# main.net
KiCad netlist of a schematic drawn in EAGLE
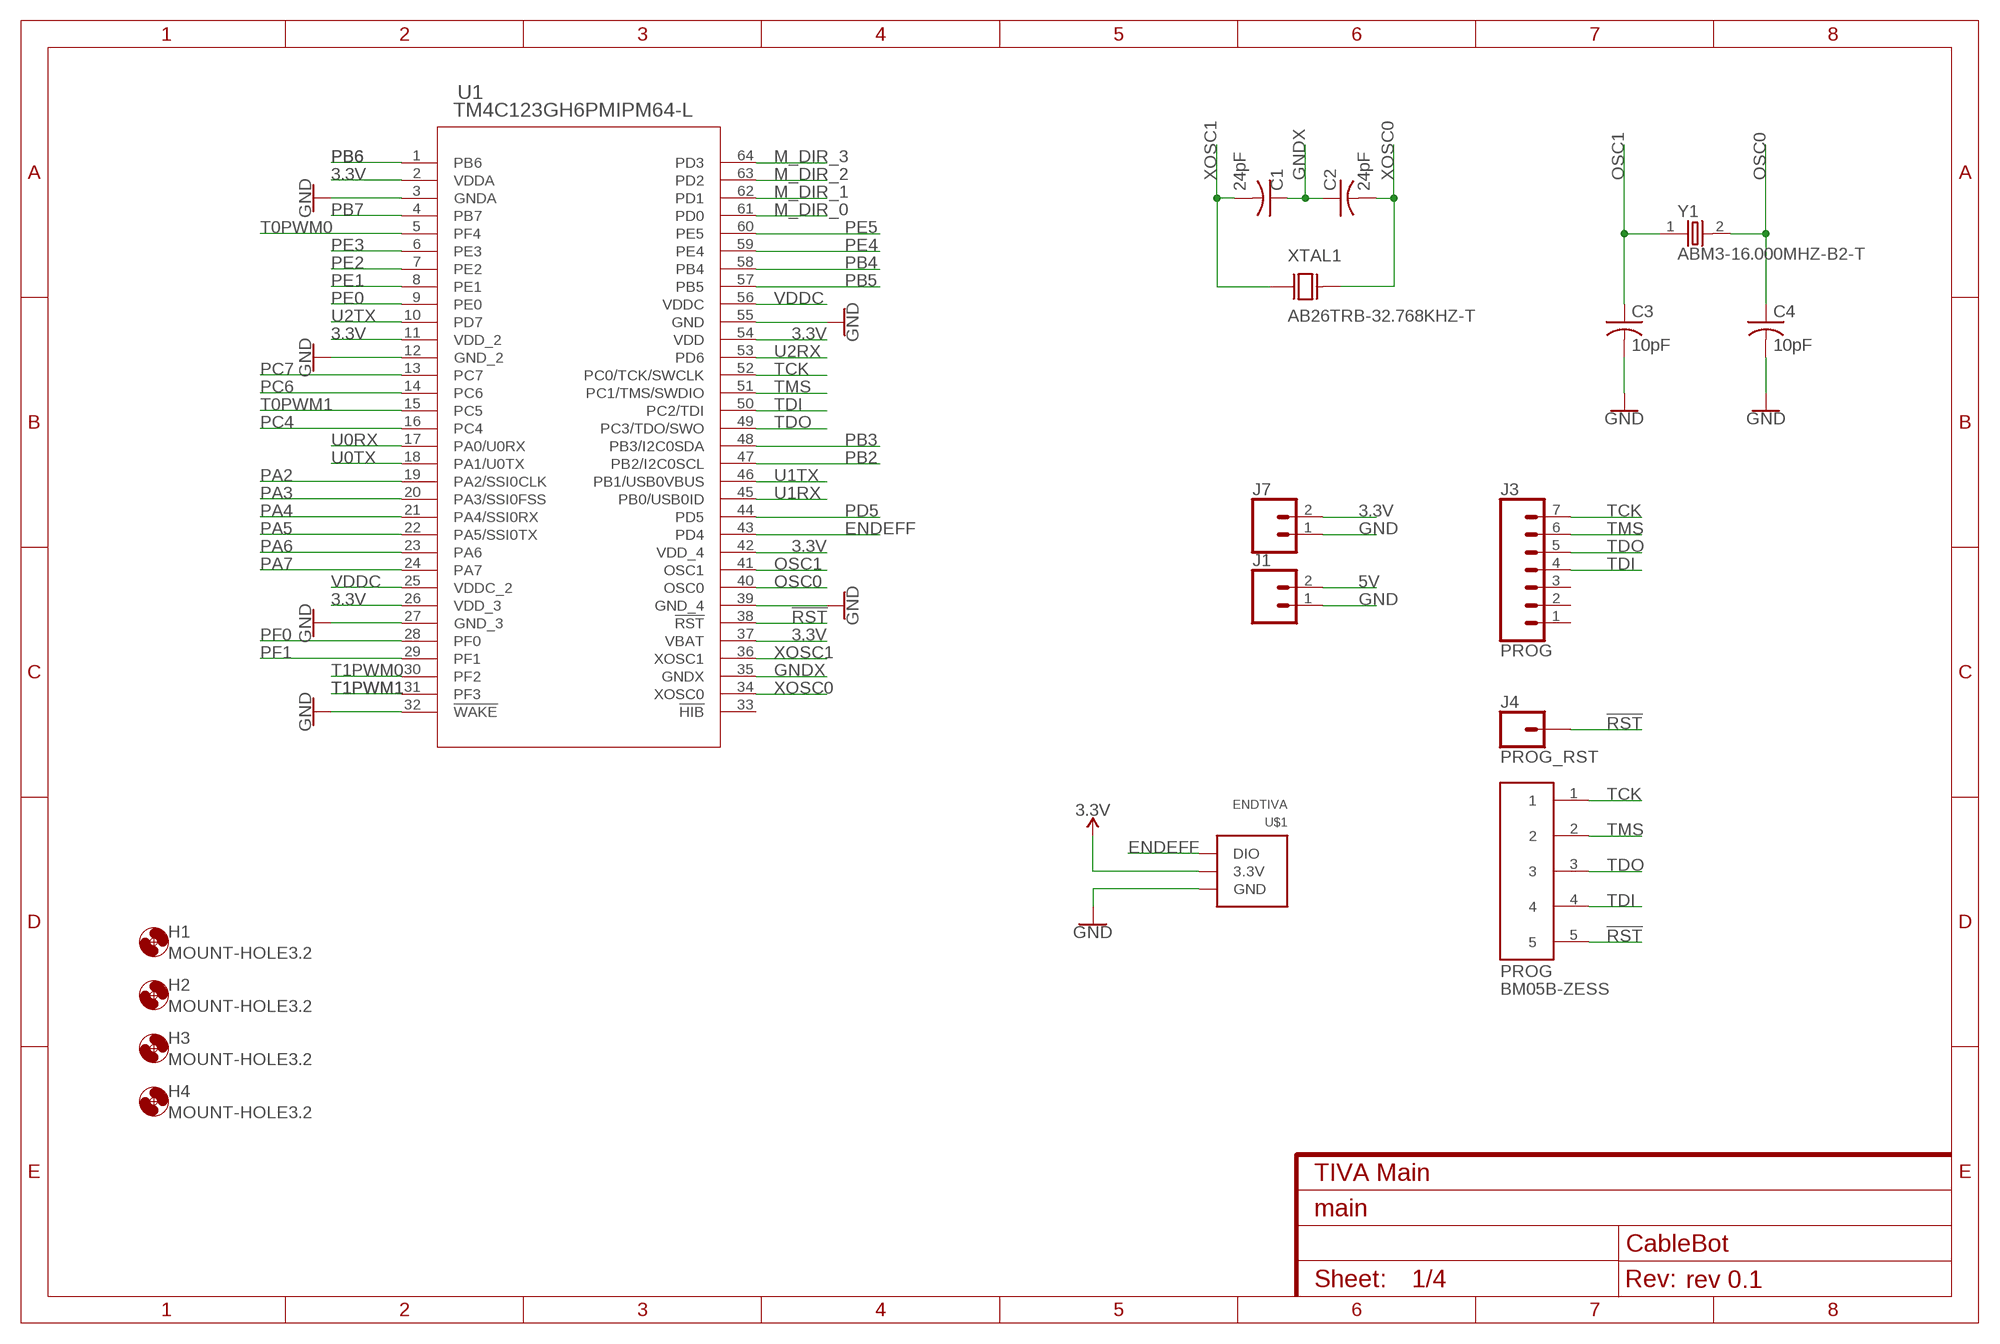
[diagram p0: schematic, sheet 1]
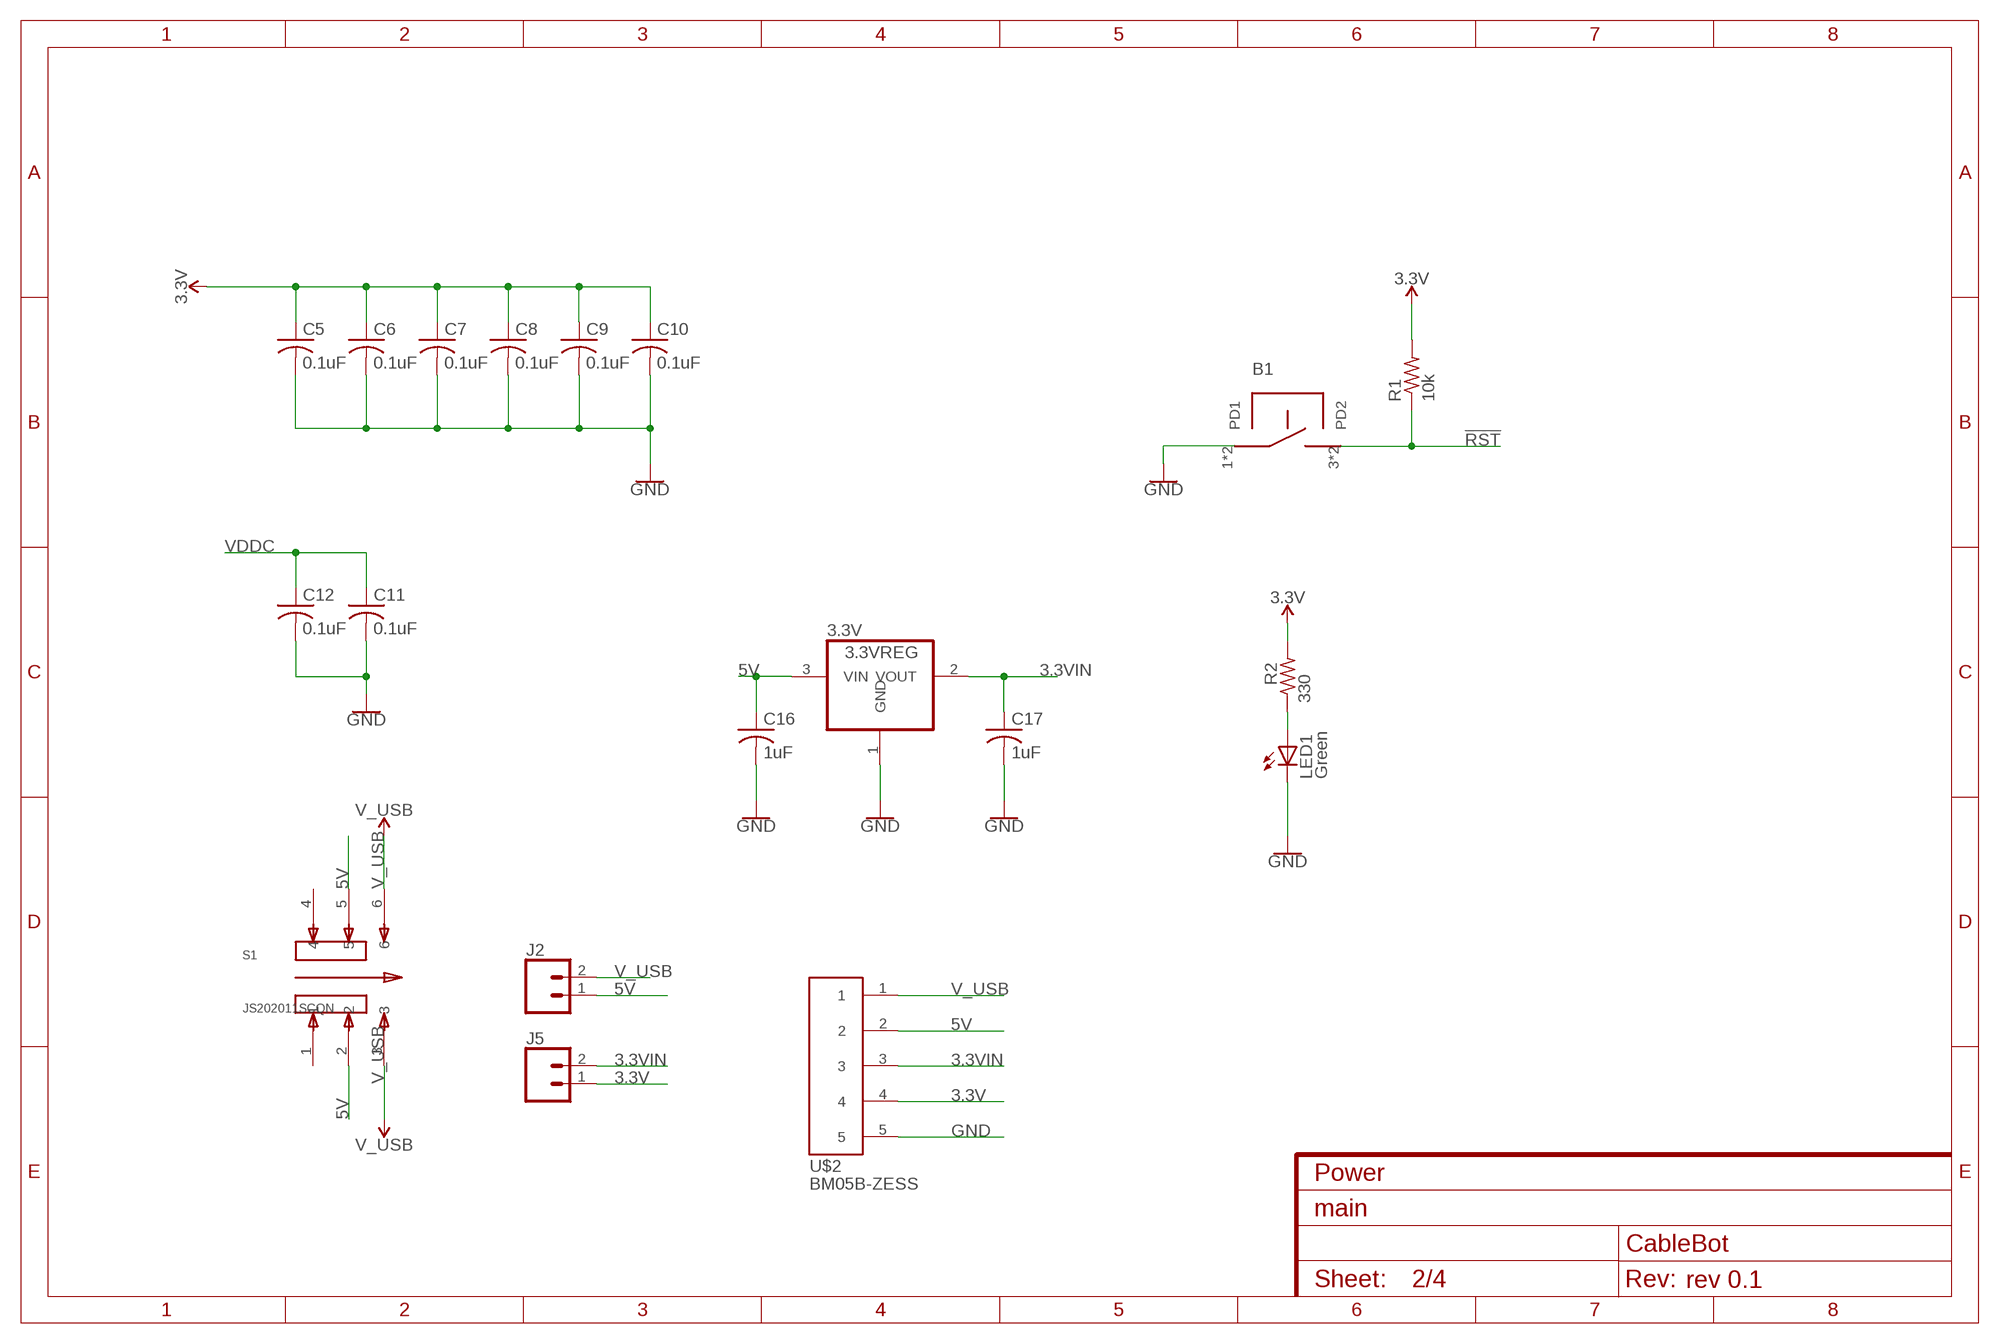
[diagram p1: schematic, sheet 2]
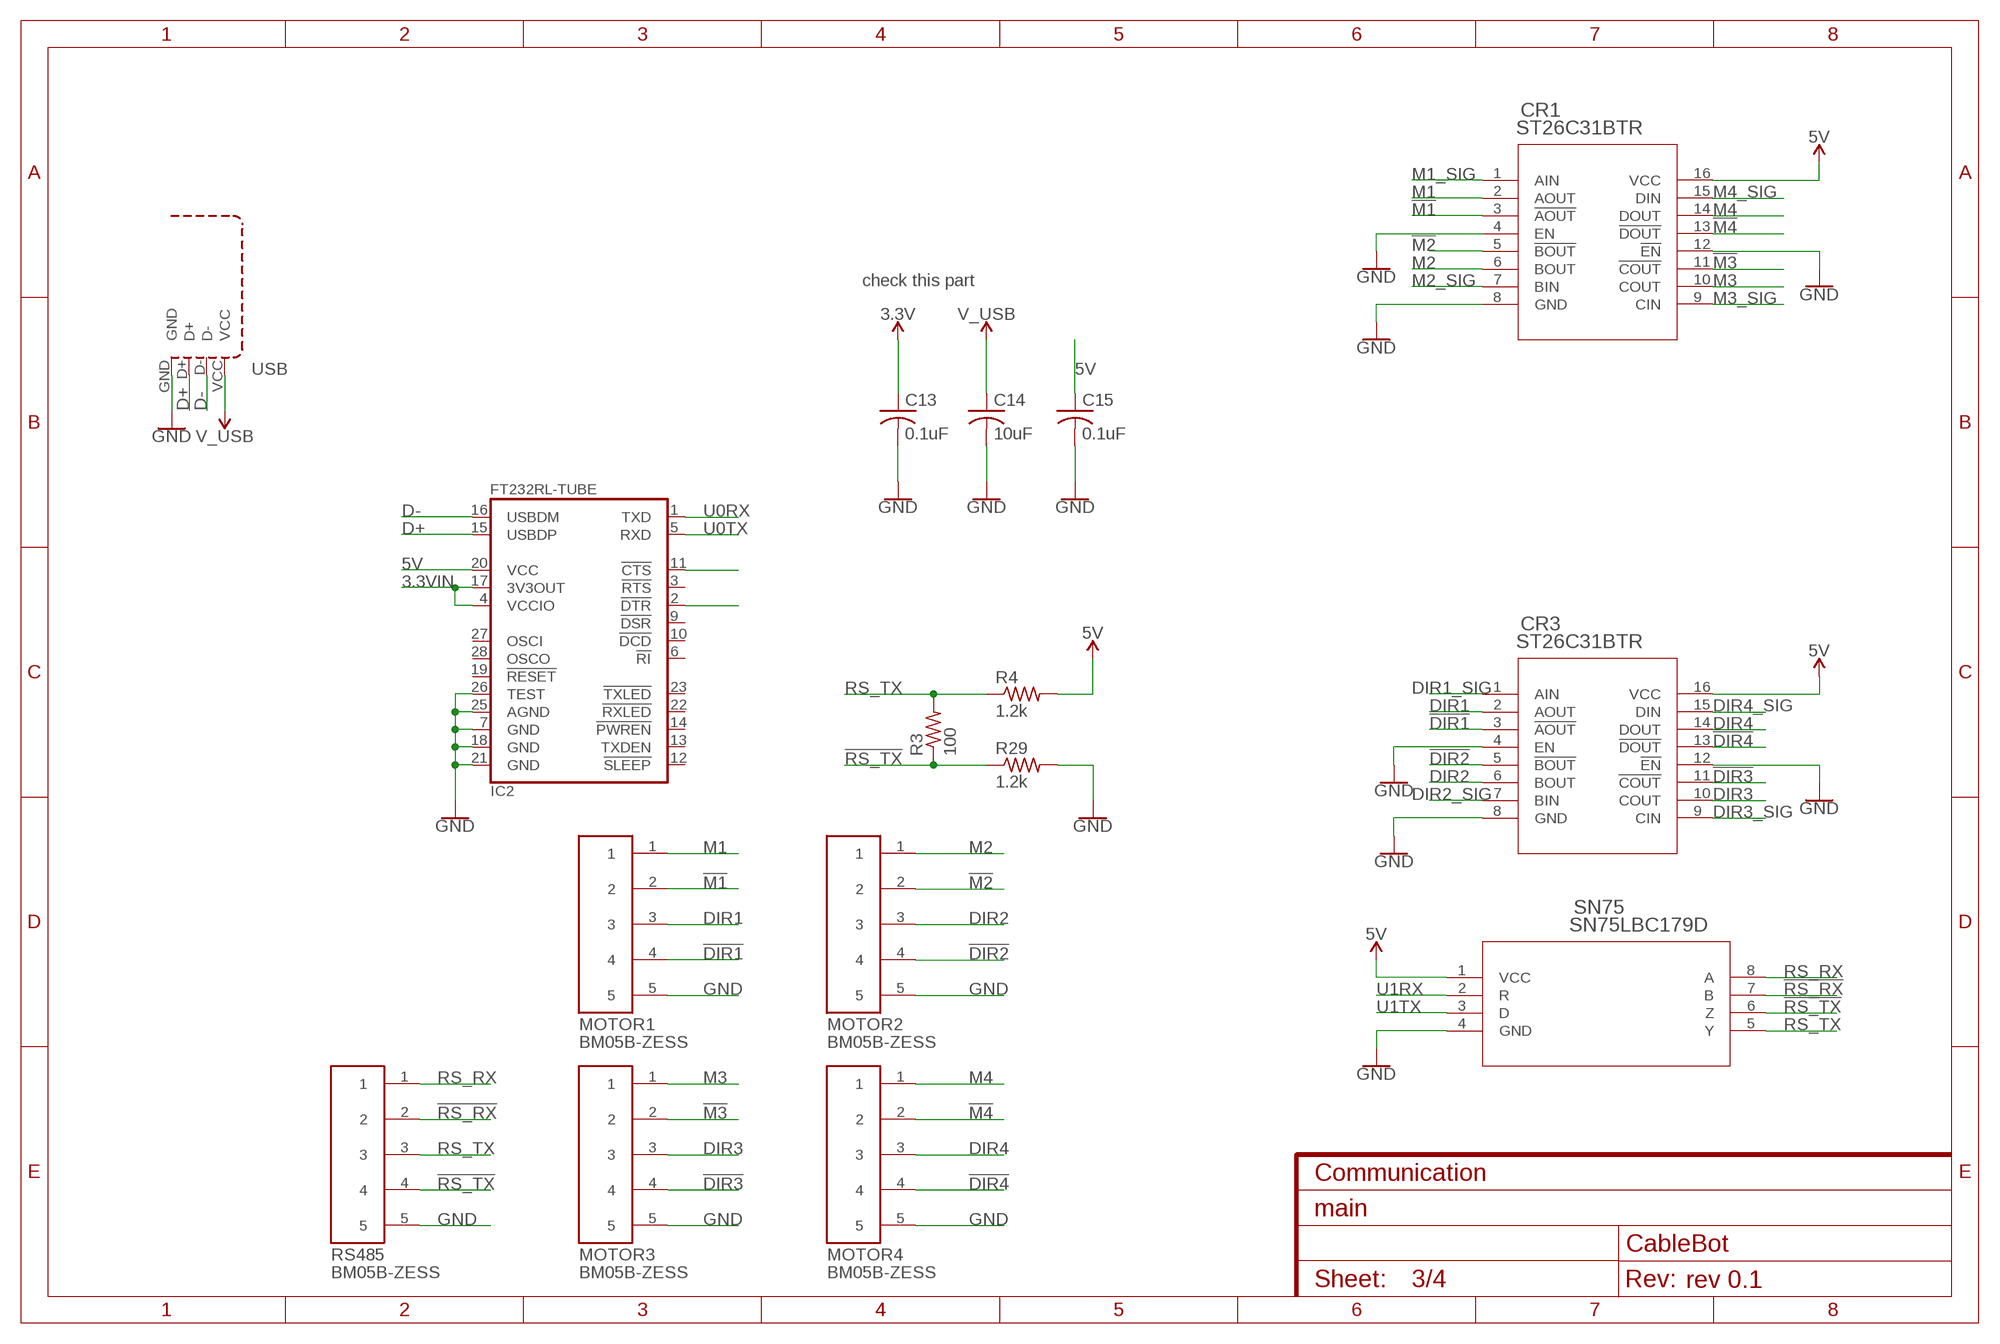
[diagram p2: schematic, sheet 3]
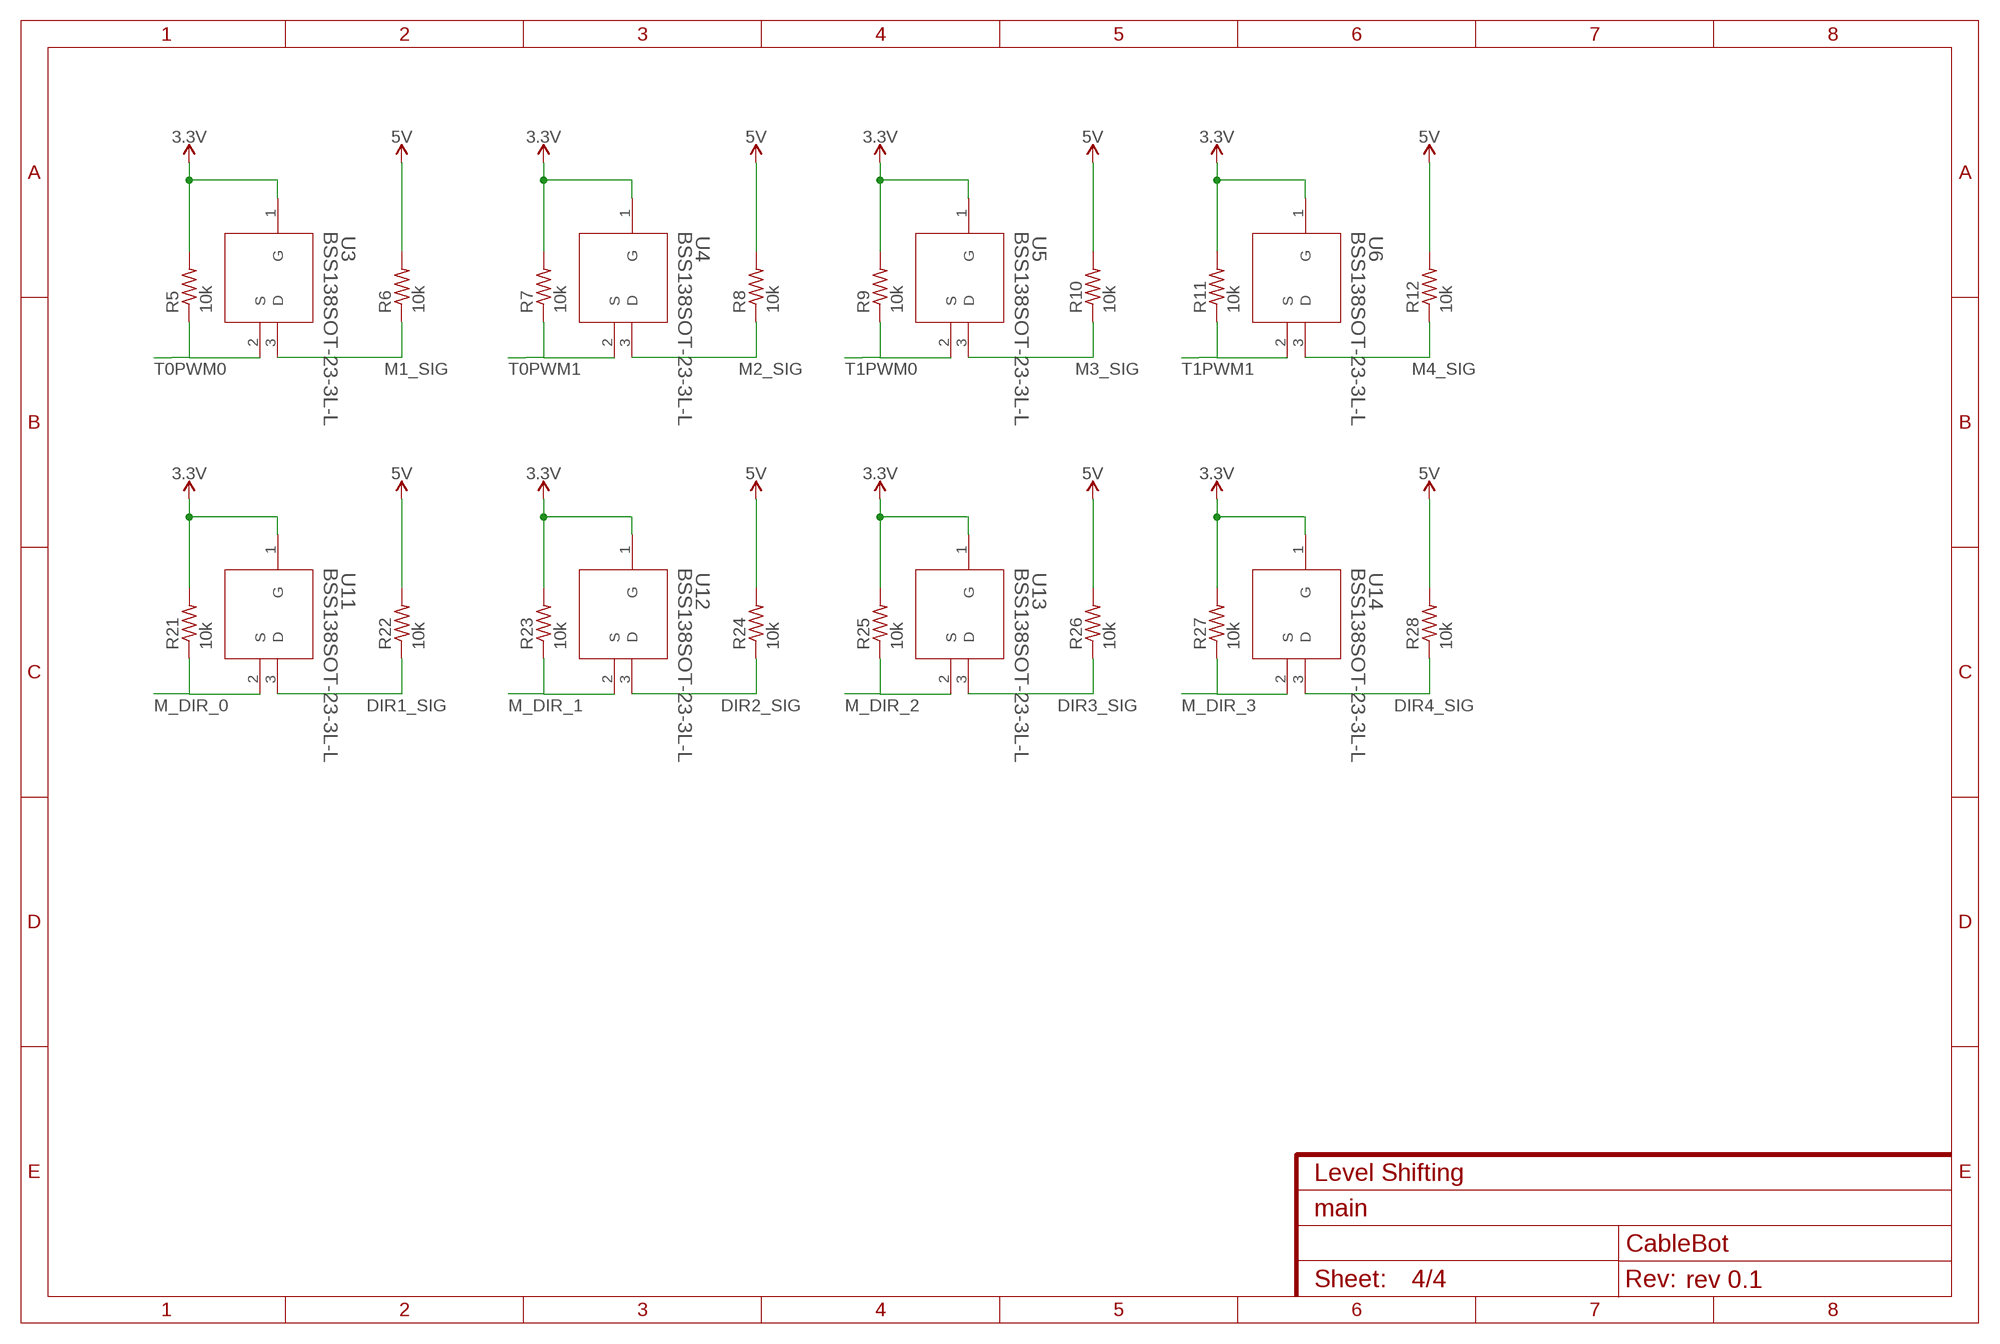
[diagram p3: schematic, sheet 4]

(export (version "E")
  (design (tool "Eeschema 10.0.6"))
  (components
    (comp (ref "3.3V")
      (value "3.3VREG")
      (footprint "eagle-import:SOT223")
      (fields (field (name "MPN") "REG1117"))
      (libsource (lib "eagle-import") (part "REG1117"))
    )
    (comp (ref "B1")
      (value "B3S-1000")
      (footprint "eagle-import:SWITCH")
      (libsource (lib "eagle-import") (part "B3S-1000"))
    )
    (comp (ref "C5")
      (value "0.1uF")
      (footprint "eagle-import:C0805")
      (libsource (lib "eagle-import") (part "C-USC0805"))
    )
    (comp (ref "C6")
      (value "0.1uF")
      (footprint "eagle-import:C0805")
      (libsource (lib "eagle-import") (part "C-USC0805"))
    )
    (comp (ref "C7")
      (value "0.1uF")
      (footprint "eagle-import:C0805")
      (libsource (lib "eagle-import") (part "C-USC0805"))
    )
    (comp (ref "C8")
      (value "0.1uF")
      (footprint "eagle-import:C0805")
      (libsource (lib "eagle-import") (part "C-USC0805"))
    )
    (comp (ref "C9")
      (value "0.1uF")
      (footprint "eagle-import:C0805")
      (libsource (lib "eagle-import") (part "C-USC0805"))
    )
    (comp (ref "C10")
      (value "0.1uF")
      (footprint "eagle-import:C0805")
      (libsource (lib "eagle-import") (part "C-USC0805"))
    )
    (comp (ref "C11")
      (value "0.1uF")
      (footprint "eagle-import:C0805")
      (libsource (lib "eagle-import") (part "C-USC0805"))
    )
    (comp (ref "C12")
      (value "0.1uF")
      (footprint "eagle-import:C0805")
      (libsource (lib "eagle-import") (part "C-USC0805"))
    )
    (comp (ref "C16")
      (value "1uF")
      (footprint "eagle-import:C0805")
      (libsource (lib "eagle-import") (part "C-USC0805"))
    )
    (comp (ref "C17")
      (value "1uF")
      (footprint "eagle-import:C0805")
      (libsource (lib "eagle-import") (part "C-USC0805"))
    )
    (comp (ref "J2")
      (value "CONN_02")
      (footprint "eagle-import:1X02")
      (libsource (lib "eagle-import") (part "CONN_02"))
    )
    (comp (ref "J5")
      (value "CONN_02")
      (footprint "eagle-import:1X02")
      (libsource (lib "eagle-import") (part "CONN_02"))
    )
    (comp (ref "LED1")
      (value "Green")
      (footprint "eagle-import:CHIP-LED0805")
      (libsource (lib "eagle-import") (part "LEDCHIP-LED0805"))
    )
    (comp (ref "R1")
      (value "10k")
      (footprint "eagle-import:R0603")
      (libsource (lib "eagle-import") (part "adafruit_420_R-US_R0603"))
    )
    (comp (ref "R2")
      (value "330")
      (footprint "eagle-import:R0805")
      (libsource (lib "eagle-import") (part "adafruit_420_R-US_R0805"))
    )
    (comp (ref "S1")
      (value "JS202011SCQN")
      (footprint "eagle-import:SW_JS202011SCQN")
      (fields (field (name "MF") "C&K"))
      (libsource (lib "eagle-import") (part "JS202011SCQN"))
    )
    (comp (ref "U$2")
      (value "BM05B-ZESS")
      (footprint "eagle-import:BM05B-ZESS")
      (libsource (lib "eagle-import") (part "BM05B-ZESS"))
    )
    (comp (ref "C1")
      (value "24pF")
      (footprint "eagle-import:C0805")
      (libsource (lib "eagle-import") (part "C-USC0805"))
    )
    (comp (ref "C2")
      (value "24pF")
      (footprint "eagle-import:C0805")
      (libsource (lib "eagle-import") (part "C-USC0805"))
    )
    (comp (ref "C3")
      (value "10pF")
      (footprint "eagle-import:C0805")
      (libsource (lib "eagle-import") (part "C-USC0805"))
    )
    (comp (ref "C4")
      (value "10pF")
      (footprint "eagle-import:C0805")
      (libsource (lib "eagle-import") (part "C-USC0805"))
    )
    (comp (ref "H1")
      (value "MOUNT-HOLE3.2")
      (footprint "eagle-import:3,2")
      (libsource (lib "eagle-import") (part "MOUNT-HOLE3.2"))
    )
    (comp (ref "H2")
      (value "MOUNT-HOLE3.2")
      (footprint "eagle-import:3,2")
      (libsource (lib "eagle-import") (part "MOUNT-HOLE3.2"))
    )
    (comp (ref "H3")
      (value "MOUNT-HOLE3.2")
      (footprint "eagle-import:3,2")
      (libsource (lib "eagle-import") (part "MOUNT-HOLE3.2"))
    )
    (comp (ref "H4")
      (value "MOUNT-HOLE3.2")
      (footprint "eagle-import:3,2")
      (libsource (lib "eagle-import") (part "MOUNT-HOLE3.2"))
    )
    (comp (ref "J1")
      (value "CONN_02")
      (footprint "eagle-import:1X02")
      (libsource (lib "eagle-import") (part "CONN_02"))
    )
    (comp (ref "J3")
      (value "PROG")
      (footprint "eagle-import:1X07")
      (libsource (lib "eagle-import") (part "CONN_07"))
    )
    (comp (ref "J4")
      (value "PROG_RST")
      (footprint "eagle-import:1X01")
      (libsource (lib "eagle-import") (part "CONN_01"))
    )
    (comp (ref "J7")
      (value "CONN_02")
      (footprint "eagle-import:1X02")
      (libsource (lib "eagle-import") (part "CONN_02"))
    )
    (comp (ref "PROG")
      (value "BM05B-ZESS")
      (footprint "eagle-import:BM05B-ZESS")
      (libsource (lib "eagle-import") (part "BM05B-ZESS"))
    )
    (comp (ref "U$1")
      (value "ENDTIVA")
      (footprint "eagle-import:ENDTIVA")
      (libsource (lib "eagle-import") (part "ENDTIVA"))
    )
    (comp (ref "U1")
      (value "TM4C123GH6PMIPM64-L")
      (footprint "eagle-import:PM64-L")
      (fields (field (name "MANUFACTURER_PART_NUMBER") "TM4C123GH6PMI"))
      (libsource (lib "eagle-import") (part "TM4C123GH6PMIPM64-L"))
    )
    (comp (ref "XTAL1")
      (value "AB26TRB-32.768KHZ-T")
      (footprint "eagle-import:XTAL_AB26TRB-32.768KHZ-T")
      (fields (field (name "DIGI-KEY_PART_NUMBER") "535-9033-1-ND") (field (name "MF") "Abracon"))
      (libsource (lib "eagle-import") (part "AB26TRB-32.768KHZ-T"))
    )
    (comp (ref "Y1")
      (value "ABM3-16.000MHZ-B2-T")
      (footprint "eagle-import:XTAL500X320X130N")
      (fields (field (name "DIGI-KEY_PART_NUMBER") "535-9103-1-ND") (field (name "MF") "Abracon"))
      (libsource (lib "eagle-import") (part "ABM3-16.000MHZ-B2-T"))
    )
    (comp (ref "R5")
      (value "10k")
      (footprint "eagle-import:R0603")
      (libsource (lib "eagle-import") (part "R-US_R0603"))
    )
    (comp (ref "R6")
      (value "10k")
      (footprint "eagle-import:R0603")
      (libsource (lib "eagle-import") (part "R-US_R0603"))
    )
    (comp (ref "R7")
      (value "10k")
      (footprint "eagle-import:R0603")
      (libsource (lib "eagle-import") (part "R-US_R0603"))
    )
    (comp (ref "R8")
      (value "10k")
      (footprint "eagle-import:R0603")
      (libsource (lib "eagle-import") (part "R-US_R0603"))
    )
    (comp (ref "R9")
      (value "10k")
      (footprint "eagle-import:R0603")
      (libsource (lib "eagle-import") (part "R-US_R0603"))
    )
    (comp (ref "R10")
      (value "10k")
      (footprint "eagle-import:R0603")
      (libsource (lib "eagle-import") (part "R-US_R0603"))
    )
    (comp (ref "R11")
      (value "10k")
      (footprint "eagle-import:R0603")
      (libsource (lib "eagle-import") (part "R-US_R0603"))
    )
    (comp (ref "R12")
      (value "10k")
      (footprint "eagle-import:R0603")
      (libsource (lib "eagle-import") (part "R-US_R0603"))
    )
    (comp (ref "R21")
      (value "10k")
      (footprint "eagle-import:R0603")
      (libsource (lib "eagle-import") (part "R-US_R0603"))
    )
    (comp (ref "R22")
      (value "10k")
      (footprint "eagle-import:R0603")
      (libsource (lib "eagle-import") (part "R-US_R0603"))
    )
    (comp (ref "R23")
      (value "10k")
      (footprint "eagle-import:R0603")
      (libsource (lib "eagle-import") (part "R-US_R0603"))
    )
    (comp (ref "R24")
      (value "10k")
      (footprint "eagle-import:R0603")
      (libsource (lib "eagle-import") (part "R-US_R0603"))
    )
    (comp (ref "R25")
      (value "10k")
      (footprint "eagle-import:R0603")
      (libsource (lib "eagle-import") (part "R-US_R0603"))
    )
    (comp (ref "R26")
      (value "10k")
      (footprint "eagle-import:R0603")
      (libsource (lib "eagle-import") (part "R-US_R0603"))
    )
    (comp (ref "R27")
      (value "10k")
      (footprint "eagle-import:R0603")
      (libsource (lib "eagle-import") (part "R-US_R0603"))
    )
    (comp (ref "R28")
      (value "10k")
      (footprint "eagle-import:R0603")
      (libsource (lib "eagle-import") (part "R-US_R0603"))
    )
    (comp (ref "U3")
      (value "BSS138SOT-23-3L-L")
      (footprint "eagle-import:SOT-23-3L-L")
      (fields (field (name "MANUFACTURER_PART_NUMBER") "BSS138"))
      (libsource (lib "eagle-import") (part "BSS138SOT-23-3L-L"))
    )
    (comp (ref "U4")
      (value "BSS138SOT-23-3L-L")
      (footprint "eagle-import:SOT-23-3L-L")
      (fields (field (name "MANUFACTURER_PART_NUMBER") "BSS138"))
      (libsource (lib "eagle-import") (part "BSS138SOT-23-3L-L"))
    )
    (comp (ref "U5")
      (value "BSS138SOT-23-3L-L")
      (footprint "eagle-import:SOT-23-3L-L")
      (fields (field (name "MANUFACTURER_PART_NUMBER") "BSS138"))
      (libsource (lib "eagle-import") (part "BSS138SOT-23-3L-L"))
    )
    (comp (ref "U6")
      (value "BSS138SOT-23-3L-L")
      (footprint "eagle-import:SOT-23-3L-L")
      (fields (field (name "MANUFACTURER_PART_NUMBER") "BSS138"))
      (libsource (lib "eagle-import") (part "BSS138SOT-23-3L-L"))
    )
    (comp (ref "U11")
      (value "BSS138SOT-23-3L-L")
      (footprint "eagle-import:SOT-23-3L-L")
      (fields (field (name "MANUFACTURER_PART_NUMBER") "BSS138"))
      (libsource (lib "eagle-import") (part "BSS138SOT-23-3L-L"))
    )
    (comp (ref "U12")
      (value "BSS138SOT-23-3L-L")
      (footprint "eagle-import:SOT-23-3L-L")
      (fields (field (name "MANUFACTURER_PART_NUMBER") "BSS138"))
      (libsource (lib "eagle-import") (part "BSS138SOT-23-3L-L"))
    )
    (comp (ref "U13")
      (value "BSS138SOT-23-3L-L")
      (footprint "eagle-import:SOT-23-3L-L")
      (fields (field (name "MANUFACTURER_PART_NUMBER") "BSS138"))
      (libsource (lib "eagle-import") (part "BSS138SOT-23-3L-L"))
    )
    (comp (ref "U14")
      (value "BSS138SOT-23-3L-L")
      (footprint "eagle-import:SOT-23-3L-L")
      (fields (field (name "MANUFACTURER_PART_NUMBER") "BSS138"))
      (libsource (lib "eagle-import") (part "BSS138SOT-23-3L-L"))
    )
    (comp (ref "C13")
      (value "0.1uF")
      (footprint "eagle-import:C0805")
      (libsource (lib "eagle-import") (part "C-USC0805"))
    )
    (comp (ref "C14")
      (value "10uF")
      (footprint "eagle-import:C0805")
      (libsource (lib "eagle-import") (part "C-USC0805"))
    )
    (comp (ref "C15")
      (value "0.1uF")
      (footprint "eagle-import:C0805")
      (libsource (lib "eagle-import") (part "C-USC0805"))
    )
    (comp (ref "CR1")
      (value "ST26C31BTR")
      (footprint "eagle-import:TSSOP16")
      (libsource (lib "eagle-import") (part "ST26C31BTR"))
    )
    (comp (ref "CR3")
      (value "ST26C31BTR")
      (footprint "eagle-import:TSSOP16")
      (libsource (lib "eagle-import") (part "ST26C31BTR"))
    )
    (comp (ref "IC2")
      (value "FT232RL-TUBE")
      (footprint "eagle-import:SSOP28-LD")
      (fields (field (name "DIGI-KEY_PART_NUMBER") "768-1306-ND") (field (name "MF") "FTDI,"))
      (libsource (lib "eagle-import") (part "FT232RL-TUBE"))
    )
    (comp (ref "MOTOR1")
      (value "BM05B-ZESS")
      (footprint "eagle-import:BM05B-ZESS")
      (libsource (lib "eagle-import") (part "BM05B-ZESS"))
    )
    (comp (ref "MOTOR2")
      (value "BM05B-ZESS")
      (footprint "eagle-import:BM05B-ZESS")
      (libsource (lib "eagle-import") (part "BM05B-ZESS"))
    )
    (comp (ref "MOTOR3")
      (value "BM05B-ZESS")
      (footprint "eagle-import:BM05B-ZESS")
      (libsource (lib "eagle-import") (part "BM05B-ZESS"))
    )
    (comp (ref "MOTOR4")
      (value "BM05B-ZESS")
      (footprint "eagle-import:BM05B-ZESS")
      (libsource (lib "eagle-import") (part "BM05B-ZESS"))
    )
    (comp (ref "R3")
      (value "100")
      (footprint "eagle-import:R0805")
      (libsource (lib "eagle-import") (part "resistor_348_R-US_R0805"))
    )
    (comp (ref "R4")
      (value "1.2k")
      (footprint "eagle-import:R0805")
      (libsource (lib "eagle-import") (part "resistor_348_R-US_R0805"))
    )
    (comp (ref "R29")
      (value "1.2k")
      (footprint "eagle-import:R0805")
      (libsource (lib "eagle-import") (part "resistor_348_R-US_R0805"))
    )
    (comp (ref "RS485")
      (value "BM05B-ZESS")
      (footprint "eagle-import:BM05B-ZESS")
      (libsource (lib "eagle-import") (part "BM05B-ZESS"))
    )
    (comp (ref "SN75")
      (value "SN75LBC179D")
      (footprint "eagle-import:D8")
      (libsource (lib "eagle-import") (part "SN75LBC179D"))
    )
    (comp (ref "USB")
      (value "ZX62MICROUSB")
      (footprint "eagle-import:ZX62-AB-5PA(11)")
      (libsource (lib "eagle-import") (part "ZX62MICROUSB"))
    )
  )
  (nets
    (net (code "1") (name "3.3V") (class "Default")
      (node (ref "C10") (pin "1") (pinfunction "1_1") (pintype "passive"))
      (node (ref "C13") (pin "1") (pinfunction "1_1") (pintype "passive"))
      (node (ref "C5") (pin "1") (pinfunction "1_1") (pintype "passive"))
      (node (ref "C6") (pin "1") (pinfunction "1_1") (pintype "passive"))
      (node (ref "C7") (pin "1") (pinfunction "1_1") (pintype "passive"))
      (node (ref "C8") (pin "1") (pinfunction "1_1") (pintype "passive"))
      (node (ref "C9") (pin "1") (pinfunction "1_1") (pintype "passive"))
      (node (ref "J5") (pin "1") (pinfunction "1_1") (pintype "passive"))
      (node (ref "J7") (pin "2") (pinfunction "2_2") (pintype "passive"))
      (node (ref "R1") (pin "2") (pinfunction "2_2") (pintype "passive"))
      (node (ref "R11") (pin "2") (pinfunction "2_2") (pintype "passive"))
      (node (ref "R2") (pin "2") (pinfunction "2_2") (pintype "passive"))
      (node (ref "R21") (pin "2") (pinfunction "2_2") (pintype "passive"))
      (node (ref "R23") (pin "2") (pinfunction "2_2") (pintype "passive"))
      (node (ref "R25") (pin "2") (pinfunction "2_2") (pintype "passive"))
      (node (ref "R27") (pin "2") (pinfunction "2_2") (pintype "passive"))
      (node (ref "R5") (pin "2") (pinfunction "2_2") (pintype "passive"))
      (node (ref "R7") (pin "2") (pinfunction "2_2") (pintype "passive"))
      (node (ref "R9") (pin "2") (pinfunction "2_2") (pintype "passive"))
      (node (ref "U$1") (pin "3.3V") (pinfunction "3.3V_3.3V") (pintype "bidirectional"))
      (node (ref "U$2") (pin "4") (pinfunction "4_4") (pintype "bidirectional"))
      (node (ref "U1") (pin "11") (pinfunction "VDD_2_11") (pintype "power_in"))
      (node (ref "U1") (pin "2") (pinfunction "VDDA_2") (pintype "power_in"))
      (node (ref "U1") (pin "26") (pinfunction "VDD_3_26") (pintype "power_in"))
      (node (ref "U1") (pin "37") (pinfunction "VBAT_37") (pintype "power_in"))
      (node (ref "U1") (pin "42") (pinfunction "VDD_4_42") (pintype "power_in"))
      (node (ref "U1") (pin "54") (pinfunction "VDD_54") (pintype "power_in"))
      (node (ref "U11") (pin "1") (pinfunction "G_1") (pintype "passive"))
      (node (ref "U12") (pin "1") (pinfunction "G_1") (pintype "passive"))
      (node (ref "U13") (pin "1") (pinfunction "G_1") (pintype "passive"))
      (node (ref "U14") (pin "1") (pinfunction "G_1") (pintype "passive"))
      (node (ref "U3") (pin "1") (pinfunction "G_1") (pintype "passive"))
      (node (ref "U4") (pin "1") (pinfunction "G_1") (pintype "passive"))
      (node (ref "U5") (pin "1") (pinfunction "G_1") (pintype "passive"))
      (node (ref "U6") (pin "1") (pinfunction "G_1") (pintype "passive"))
    )
    (net (code "2") (name "3.3VIN") (class "Default")
      (node (ref "3.3V") (pin "2") (pinfunction "VOUT_2") (pintype "output"))
      (node (ref "C17") (pin "1") (pinfunction "1_1") (pintype "passive"))
      (node (ref "IC2") (pin "17") (pinfunction "3V3OUT_17") (pintype "power_in"))
      (node (ref "IC2") (pin "4") (pinfunction "VCCIO_4") (pintype "power_in"))
      (node (ref "J5") (pin "2") (pinfunction "2_2") (pintype "passive"))
      (node (ref "U$2") (pin "3") (pinfunction "3_3") (pintype "bidirectional"))
    )
    (net (code "3") (name "5V") (class "Default")
      (node (ref "3.3V") (pin "3") (pinfunction "VIN_3") (pintype "input"))
      (node (ref "C15") (pin "1") (pinfunction "1_1") (pintype "passive"))
      (node (ref "C16") (pin "1") (pinfunction "1_1") (pintype "passive"))
      (node (ref "CR1") (pin "16") (pinfunction "VCC_16") (pintype "power_in"))
      (node (ref "CR3") (pin "16") (pinfunction "VCC_16") (pintype "power_in"))
      (node (ref "IC2") (pin "20") (pinfunction "VCC_20") (pintype "power_in"))
      (node (ref "J1") (pin "2") (pinfunction "2_2") (pintype "passive"))
      (node (ref "J2") (pin "1") (pinfunction "1_1") (pintype "passive"))
      (node (ref "R10") (pin "2") (pinfunction "2_2") (pintype "passive"))
      (node (ref "R12") (pin "2") (pinfunction "2_2") (pintype "passive"))
      (node (ref "R22") (pin "2") (pinfunction "2_2") (pintype "passive"))
      (node (ref "R24") (pin "2") (pinfunction "2_2") (pintype "passive"))
      (node (ref "R26") (pin "2") (pinfunction "2_2") (pintype "passive"))
      (node (ref "R28") (pin "2") (pinfunction "2_2") (pintype "passive"))
      (node (ref "R4") (pin "2") (pinfunction "2_2") (pintype "passive"))
      (node (ref "R6") (pin "2") (pinfunction "2_2") (pintype "passive"))
      (node (ref "R8") (pin "2") (pinfunction "2_2") (pintype "passive"))
      (node (ref "S1") (pin "2") (pinfunction "2_2") (pintype "passive"))
      (node (ref "S1") (pin "5") (pinfunction "5_5") (pintype "passive"))
      (node (ref "SN75") (pin "1") (pinfunction "VCC_1") (pintype "power_in"))
      (node (ref "U$2") (pin "2") (pinfunction "2_2") (pintype "bidirectional"))
    )
    (net (code "4") (name "D+") (class "Default")
      (node (ref "IC2") (pin "15") (pinfunction "USBDP_15") (pintype "bidirectional"))
      (node (ref "USB") (pin "D+") (pinfunction "D+_D+") (pintype "passive"))
    )
    (net (code "5") (name "D-") (class "Default")
      (node (ref "IC2") (pin "16") (pinfunction "USBDM_16") (pintype "bidirectional"))
      (node (ref "USB") (pin "D-") (pinfunction "D-_D-") (pintype "passive"))
    )
    (net (code "6") (name "DIR1") (class "Default")
      (node (ref "CR3") (pin "2") (pinfunction "AOUT_2") (pintype "output"))
      (node (ref "MOTOR1") (pin "3") (pinfunction "3_3") (pintype "bidirectional"))
    )
    (net (code "7") (name "DIR1_SIG") (class "Default")
      (node (ref "CR3") (pin "1") (pinfunction "AIN_1") (pintype "input"))
      (node (ref "R22") (pin "1") (pinfunction "1_1") (pintype "passive"))
      (node (ref "U11") (pin "3") (pinfunction "D_3") (pintype "passive"))
    )
    (net (code "8") (name "DIR2") (class "Default")
      (node (ref "CR3") (pin "6") (pinfunction "BOUT_6") (pintype "output"))
      (node (ref "MOTOR2") (pin "3") (pinfunction "3_3") (pintype "bidirectional"))
    )
    (net (code "9") (name "DIR2_SIG") (class "Default")
      (node (ref "CR3") (pin "7") (pinfunction "BIN_7") (pintype "input"))
      (node (ref "R24") (pin "1") (pinfunction "1_1") (pintype "passive"))
      (node (ref "U12") (pin "3") (pinfunction "D_3") (pintype "passive"))
    )
    (net (code "10") (name "DIR3") (class "Default")
      (node (ref "CR3") (pin "10") (pinfunction "COUT_10") (pintype "output"))
      (node (ref "MOTOR3") (pin "3") (pinfunction "3_3") (pintype "bidirectional"))
    )
    (net (code "11") (name "DIR3_SIG") (class "Default")
      (node (ref "CR3") (pin "9") (pinfunction "CIN_9") (pintype "input"))
      (node (ref "R26") (pin "1") (pinfunction "1_1") (pintype "passive"))
      (node (ref "U13") (pin "3") (pinfunction "D_3") (pintype "passive"))
    )
    (net (code "12") (name "DIR4") (class "Default")
      (node (ref "CR3") (pin "14") (pinfunction "DOUT_14") (pintype "output"))
      (node (ref "MOTOR4") (pin "3") (pinfunction "3_3") (pintype "bidirectional"))
    )
    (net (code "13") (name "DIR4_SIG") (class "Default")
      (node (ref "CR3") (pin "15") (pinfunction "DIN_15") (pintype "input"))
      (node (ref "R28") (pin "1") (pinfunction "1_1") (pintype "passive"))
      (node (ref "U14") (pin "3") (pinfunction "D_3") (pintype "passive"))
    )
    (net (code "14") (name "ENDEFF") (class "Default")
      (node (ref "U$1") (pin "DIO") (pinfunction "DIO_DIO") (pintype "bidirectional"))
      (node (ref "U1") (pin "43") (pinfunction "PD4_43") (pintype "bidirectional"))
    )
    (net (code "15") (name "GND") (class "Default")
      (node (ref "3.3V") (pin "1") (pinfunction "GND_1") (pintype "power_in"))
      (node (ref "B1") (pin "1") (pinfunction "PD1_1") (pintype "bidirectional"))
      (node (ref "B1") (pin "2") (pinfunction "PD1_2") (pintype "bidirectional"))
      (node (ref "C10") (pin "2") (pinfunction "2_2") (pintype "passive"))
      (node (ref "C11") (pin "2") (pinfunction "2_2") (pintype "passive"))
      (node (ref "C12") (pin "2") (pinfunction "2_2") (pintype "passive"))
      (node (ref "C13") (pin "2") (pinfunction "2_2") (pintype "passive"))
      (node (ref "C14") (pin "2") (pinfunction "2_2") (pintype "passive"))
      (node (ref "C15") (pin "2") (pinfunction "2_2") (pintype "passive"))
      (node (ref "C16") (pin "2") (pinfunction "2_2") (pintype "passive"))
      (node (ref "C17") (pin "2") (pinfunction "2_2") (pintype "passive"))
      (node (ref "C3") (pin "2") (pinfunction "2_2") (pintype "passive"))
      (node (ref "C4") (pin "2") (pinfunction "2_2") (pintype "passive"))
      (node (ref "C5") (pin "2") (pinfunction "2_2") (pintype "passive"))
      (node (ref "C6") (pin "2") (pinfunction "2_2") (pintype "passive"))
      (node (ref "C7") (pin "2") (pinfunction "2_2") (pintype "passive"))
      (node (ref "C8") (pin "2") (pinfunction "2_2") (pintype "passive"))
      (node (ref "C9") (pin "2") (pinfunction "2_2") (pintype "passive"))
      (node (ref "CR1") (pin "12") (pinfunction "~{EN}_12") (pintype "passive"))
      (node (ref "CR1") (pin "4") (pinfunction "EN_4") (pintype "passive"))
      (node (ref "CR1") (pin "8") (pinfunction "GND_8") (pintype "power_in"))
      (node (ref "CR3") (pin "12") (pinfunction "~{EN}_12") (pintype "passive"))
      (node (ref "CR3") (pin "4") (pinfunction "EN_4") (pintype "passive"))
      (node (ref "CR3") (pin "8") (pinfunction "GND_8") (pintype "power_in"))
      (node (ref "IC2") (pin "18") (pinfunction "GND_18") (pintype "power_in"))
      (node (ref "IC2") (pin "21") (pinfunction "GND_21") (pintype "power_in"))
      (node (ref "IC2") (pin "25") (pinfunction "AGND_25") (pintype "power_in"))
      (node (ref "IC2") (pin "26") (pinfunction "TEST_26") (pintype "input"))
      (node (ref "IC2") (pin "7") (pinfunction "GND_7") (pintype "power_in"))
      (node (ref "J1") (pin "1") (pinfunction "1_1") (pintype "passive"))
      (node (ref "J7") (pin "1") (pinfunction "1_1") (pintype "passive"))
      (node (ref "LED1") (pin "C") (pinfunction "C_C") (pintype "passive"))
      (node (ref "MOTOR1") (pin "5") (pinfunction "5_5") (pintype "bidirectional"))
      (node (ref "MOTOR2") (pin "5") (pinfunction "5_5") (pintype "bidirectional"))
      (node (ref "MOTOR3") (pin "5") (pinfunction "5_5") (pintype "bidirectional"))
      (node (ref "MOTOR4") (pin "5") (pinfunction "5_5") (pintype "bidirectional"))
      (node (ref "R29") (pin "2") (pinfunction "2_2") (pintype "passive"))
      (node (ref "RS485") (pin "5") (pinfunction "5_5") (pintype "bidirectional"))
      (node (ref "SN75") (pin "4") (pinfunction "GND_4") (pintype "power_in"))
      (node (ref "U$1") (pin "GND") (pinfunction "GND_GND") (pintype "bidirectional"))
      (node (ref "U$2") (pin "5") (pinfunction "5_5") (pintype "bidirectional"))
      (node (ref "U1") (pin "12") (pinfunction "GND_2_12") (pintype "power_in"))
      (node (ref "U1") (pin "27") (pinfunction "GND_3_27") (pintype "power_in"))
      (node (ref "U1") (pin "3") (pinfunction "GNDA_3") (pintype "power_in"))
      (node (ref "U1") (pin "32") (pinfunction "~{WAKE}_32") (pintype "input"))
      (node (ref "U1") (pin "39") (pinfunction "GND_4_39") (pintype "power_in"))
      (node (ref "U1") (pin "55") (pinfunction "GND_55") (pintype "power_in"))
      (node (ref "USB") (pin "GND") (pinfunction "GND_GND") (pintype "passive"))
    )
    (net (code "16") (name "GNDX") (class "Default")
      (node (ref "C1") (pin "1") (pinfunction "1_1") (pintype "passive"))
      (node (ref "C2") (pin "1") (pinfunction "1_1") (pintype "passive"))
      (node (ref "U1") (pin "35") (pinfunction "GNDX_35") (pintype "power_in"))
    )
    (net (code "17") (name "M1") (class "Default")
      (node (ref "CR1") (pin "2") (pinfunction "AOUT_2") (pintype "output"))
      (node (ref "MOTOR1") (pin "1") (pinfunction "1_1") (pintype "bidirectional"))
    )
    (net (code "18") (name "M1_SIG") (class "Default")
      (node (ref "CR1") (pin "1") (pinfunction "AIN_1") (pintype "input"))
      (node (ref "R6") (pin "1") (pinfunction "1_1") (pintype "passive"))
      (node (ref "U3") (pin "3") (pinfunction "D_3") (pintype "passive"))
    )
    (net (code "19") (name "M2") (class "Default")
      (node (ref "CR1") (pin "6") (pinfunction "BOUT_6") (pintype "output"))
      (node (ref "MOTOR2") (pin "1") (pinfunction "1_1") (pintype "bidirectional"))
    )
    (net (code "20") (name "M2_SIG") (class "Default")
      (node (ref "CR1") (pin "7") (pinfunction "BIN_7") (pintype "input"))
      (node (ref "R8") (pin "1") (pinfunction "1_1") (pintype "passive"))
      (node (ref "U4") (pin "3") (pinfunction "D_3") (pintype "passive"))
    )
    (net (code "21") (name "M3") (class "Default")
      (node (ref "CR1") (pin "10") (pinfunction "COUT_10") (pintype "output"))
      (node (ref "MOTOR3") (pin "1") (pinfunction "1_1") (pintype "bidirectional"))
    )
    (net (code "22") (name "M3_SIG") (class "Default")
      (node (ref "CR1") (pin "9") (pinfunction "CIN_9") (pintype "input"))
      (node (ref "R10") (pin "1") (pinfunction "1_1") (pintype "passive"))
      (node (ref "U5") (pin "3") (pinfunction "D_3") (pintype "passive"))
    )
    (net (code "23") (name "M4") (class "Default")
      (node (ref "CR1") (pin "14") (pinfunction "DOUT_14") (pintype "output"))
      (node (ref "MOTOR4") (pin "1") (pinfunction "1_1") (pintype "bidirectional"))
    )
    (net (code "24") (name "M4_SIG") (class "Default")
      (node (ref "CR1") (pin "15") (pinfunction "DIN_15") (pintype "input"))
      (node (ref "R12") (pin "1") (pinfunction "1_1") (pintype "passive"))
      (node (ref "U6") (pin "3") (pinfunction "D_3") (pintype "passive"))
    )
    (net (code "25") (name "M_DIR_0") (class "Default")
      (node (ref "R21") (pin "1") (pinfunction "1_1") (pintype "passive"))
      (node (ref "U1") (pin "61") (pinfunction "PD0_61") (pintype "bidirectional"))
      (node (ref "U11") (pin "2") (pinfunction "S_2") (pintype "passive"))
    )
    (net (code "26") (name "M_DIR_1") (class "Default")
      (node (ref "R23") (pin "1") (pinfunction "1_1") (pintype "passive"))
      (node (ref "U1") (pin "62") (pinfunction "PD1_62") (pintype "bidirectional"))
      (node (ref "U12") (pin "2") (pinfunction "S_2") (pintype "passive"))
    )
    (net (code "27") (name "M_DIR_2") (class "Default")
      (node (ref "R25") (pin "1") (pinfunction "1_1") (pintype "passive"))
      (node (ref "U1") (pin "63") (pinfunction "PD2_63") (pintype "bidirectional"))
      (node (ref "U13") (pin "2") (pinfunction "S_2") (pintype "passive"))
    )
    (net (code "28") (name "M_DIR_3") (class "Default")
      (node (ref "R27") (pin "1") (pinfunction "1_1") (pintype "passive"))
      (node (ref "U1") (pin "64") (pinfunction "PD3_64") (pintype "bidirectional"))
      (node (ref "U14") (pin "2") (pinfunction "S_2") (pintype "passive"))
    )
    (net (code "29") (name "Net-(LED1-PadA)") (class "Default")
      (node (ref "LED1") (pin "A") (pinfunction "A_A") (pintype "passive"))
      (node (ref "R2") (pin "1") (pinfunction "1_1") (pintype "passive"))
    )
    (net (code "30") (name "OSC0") (class "Default")
      (node (ref "C4") (pin "1") (pinfunction "1_1") (pintype "passive"))
      (node (ref "U1") (pin "40") (pinfunction "OSC0_40") (pintype "input"))
      (node (ref "Y1") (pin "2") (pinfunction "2_2") (pintype "passive"))
    )
    (net (code "31") (name "OSC1") (class "Default")
      (node (ref "C3") (pin "1") (pinfunction "1_1") (pintype "passive"))
      (node (ref "U1") (pin "41") (pinfunction "OSC1_41") (pintype "output"))
      (node (ref "Y1") (pin "1") (pinfunction "1_1") (pintype "passive"))
    )
    (net (code "32") (name "PA2") (class "Default")
      (node (ref "U1") (pin "19") (pinfunction "PA2/SSI0CLK_19") (pintype "bidirectional"))
    )
    (net (code "33") (name "PA3") (class "Default")
      (node (ref "U1") (pin "20") (pinfunction "PA3/SSI0FSS_20") (pintype "bidirectional"))
    )
    (net (code "34") (name "PA4") (class "Default")
      (node (ref "U1") (pin "21") (pinfunction "PA4/SSI0RX_21") (pintype "bidirectional"))
    )
    (net (code "35") (name "PA5") (class "Default")
      (node (ref "U1") (pin "22") (pinfunction "PA5/SSI0TX_22") (pintype "bidirectional"))
    )
    (net (code "36") (name "PA6") (class "Default")
      (node (ref "U1") (pin "23") (pinfunction "PA6_23") (pintype "bidirectional"))
    )
    (net (code "37") (name "PA7") (class "Default")
      (node (ref "U1") (pin "24") (pinfunction "PA7_24") (pintype "bidirectional"))
    )
    (net (code "38") (name "PB2") (class "Default")
      (node (ref "U1") (pin "47") (pinfunction "PB2/I2C0SCL_47") (pintype "bidirectional"))
    )
    (net (code "39") (name "PB3") (class "Default")
      (node (ref "U1") (pin "48") (pinfunction "PB3/I2C0SDA_48") (pintype "bidirectional"))
    )
    (net (code "40") (name "PB4") (class "Default")
      (node (ref "U1") (pin "58") (pinfunction "PB4_58") (pintype "bidirectional"))
    )
    (net (code "41") (name "PB5") (class "Default")
      (node (ref "U1") (pin "57") (pinfunction "PB5_57") (pintype "bidirectional"))
    )
    (net (code "42") (name "PB6") (class "Default")
      (node (ref "U1") (pin "1") (pinfunction "PB6_1") (pintype "bidirectional"))
    )
    (net (code "43") (name "PB7") (class "Default")
      (node (ref "U1") (pin "4") (pinfunction "PB7_4") (pintype "bidirectional"))
    )
    (net (code "44") (name "PC4") (class "Default")
      (node (ref "U1") (pin "16") (pinfunction "PC4_16") (pintype "bidirectional"))
    )
    (net (code "45") (name "PC6") (class "Default")
      (node (ref "U1") (pin "14") (pinfunction "PC6_14") (pintype "bidirectional"))
    )
    (net (code "46") (name "PC7") (class "Default")
      (node (ref "U1") (pin "13") (pinfunction "PC7_13") (pintype "bidirectional"))
    )
    (net (code "47") (name "PD5") (class "Default")
      (node (ref "U1") (pin "44") (pinfunction "PD5_44") (pintype "bidirectional"))
    )
    (net (code "48") (name "PE0") (class "Default")
      (node (ref "U1") (pin "9") (pinfunction "PE0_9") (pintype "bidirectional"))
    )
    (net (code "49") (name "PE1") (class "Default")
      (node (ref "U1") (pin "8") (pinfunction "PE1_8") (pintype "bidirectional"))
    )
    (net (code "50") (name "PE2") (class "Default")
      (node (ref "U1") (pin "7") (pinfunction "PE2_7") (pintype "bidirectional"))
    )
    (net (code "51") (name "PE3") (class "Default")
      (node (ref "U1") (pin "6") (pinfunction "PE3_6") (pintype "bidirectional"))
    )
    (net (code "52") (name "PE4") (class "Default")
      (node (ref "U1") (pin "59") (pinfunction "PE4_59") (pintype "bidirectional"))
    )
    (net (code "53") (name "PE5") (class "Default")
      (node (ref "U1") (pin "60") (pinfunction "PE5_60") (pintype "bidirectional"))
    )
    (net (code "54") (name "PF0") (class "Default")
      (node (ref "U1") (pin "28") (pinfunction "PF0_28") (pintype "bidirectional"))
    )
    (net (code "55") (name "PF1") (class "Default")
      (node (ref "U1") (pin "29") (pinfunction "PF1_29") (pintype "bidirectional"))
    )
    (net (code "56") (name "RS_RX") (class "Default")
      (node (ref "RS485") (pin "1") (pinfunction "1_1") (pintype "bidirectional"))
      (node (ref "SN75") (pin "8") (pinfunction "A_8") (pintype "output"))
    )
    (net (code "57") (name "RS_TX") (class "Default")
      (node (ref "R3") (pin "2") (pinfunction "2_2") (pintype "passive"))
      (node (ref "R4") (pin "1") (pinfunction "1_1") (pintype "passive"))
      (node (ref "RS485") (pin "3") (pinfunction "3_3") (pintype "bidirectional"))
      (node (ref "SN75") (pin "5") (pinfunction "Y_5") (pintype "output"))
    )
    (net (code "58") (name "T0PWM0") (class "Default")
      (node (ref "R5") (pin "1") (pinfunction "1_1") (pintype "passive"))
      (node (ref "U1") (pin "5") (pinfunction "PF4_5") (pintype "bidirectional"))
      (node (ref "U3") (pin "2") (pinfunction "S_2") (pintype "passive"))
    )
    (net (code "59") (name "T0PWM1") (class "Default")
      (node (ref "R7") (pin "1") (pinfunction "1_1") (pintype "passive"))
      (node (ref "U1") (pin "15") (pinfunction "PC5_15") (pintype "bidirectional"))
      (node (ref "U4") (pin "2") (pinfunction "S_2") (pintype "passive"))
    )
    (net (code "60") (name "T1PWM0") (class "Default")
      (node (ref "R9") (pin "1") (pinfunction "1_1") (pintype "passive"))
      (node (ref "U1") (pin "30") (pinfunction "PF2_30") (pintype "bidirectional"))
      (node (ref "U5") (pin "2") (pinfunction "S_2") (pintype "passive"))
    )
    (net (code "61") (name "T1PWM1") (class "Default")
      (node (ref "R11") (pin "1") (pinfunction "1_1") (pintype "passive"))
      (node (ref "U1") (pin "31") (pinfunction "PF3_31") (pintype "bidirectional"))
      (node (ref "U6") (pin "2") (pinfunction "S_2") (pintype "passive"))
    )
    (net (code "62") (name "TCK") (class "Default")
      (node (ref "J3") (pin "7") (pinfunction "7_7") (pintype "passive"))
      (node (ref "PROG") (pin "1") (pinfunction "1_1") (pintype "bidirectional"))
      (node (ref "U1") (pin "52") (pinfunction "PC0/TCK/SWCLK_52") (pintype "bidirectional"))
    )
    (net (code "63") (name "TDI") (class "Default")
      (node (ref "J3") (pin "4") (pinfunction "4_4") (pintype "passive"))
      (node (ref "PROG") (pin "4") (pinfunction "4_4") (pintype "bidirectional"))
      (node (ref "U1") (pin "50") (pinfunction "PC2/TDI_50") (pintype "bidirectional"))
    )
    (net (code "64") (name "TDO") (class "Default")
      (node (ref "J3") (pin "5") (pinfunction "5_5") (pintype "passive"))
      (node (ref "PROG") (pin "3") (pinfunction "3_3") (pintype "bidirectional"))
      (node (ref "U1") (pin "49") (pinfunction "PC3/TDO/SWO_49") (pintype "bidirectional"))
    )
    (net (code "65") (name "TMS") (class "Default")
      (node (ref "J3") (pin "6") (pinfunction "6_6") (pintype "passive"))
      (node (ref "PROG") (pin "2") (pinfunction "2_2") (pintype "bidirectional"))
      (node (ref "U1") (pin "51") (pinfunction "PC1/TMS/SWDIO_51") (pintype "bidirectional"))
    )
    (net (code "66") (name "U0RX") (class "Default")
      (node (ref "IC2") (pin "1") (pinfunction "TXD_1") (pintype "output"))
      (node (ref "U1") (pin "17") (pinfunction "PA0/U0RX_17") (pintype "bidirectional"))
    )
    (net (code "67") (name "U0TX") (class "Default")
      (node (ref "IC2") (pin "5") (pinfunction "RXD_5") (pintype "input"))
      (node (ref "U1") (pin "18") (pinfunction "PA1/U0TX_18") (pintype "bidirectional"))
    )
    (net (code "68") (name "U1RX") (class "Default")
      (node (ref "SN75") (pin "2") (pinfunction "R_2") (pintype "input"))
      (node (ref "U1") (pin "45") (pinfunction "PB0/USB0ID_45") (pintype "bidirectional"))
    )
    (net (code "69") (name "U1TX") (class "Default")
      (node (ref "SN75") (pin "3") (pinfunction "D_3") (pintype "input"))
      (node (ref "U1") (pin "46") (pinfunction "PB1/USB0VBUS_46") (pintype "bidirectional"))
    )
    (net (code "70") (name "U2RX") (class "Default")
      (node (ref "U1") (pin "53") (pinfunction "PD6_53") (pintype "bidirectional"))
    )
    (net (code "71") (name "U2TX") (class "Default")
      (node (ref "U1") (pin "10") (pinfunction "PD7_10") (pintype "bidirectional"))
    )
    (net (code "72") (name "VDDC") (class "Default")
      (node (ref "C11") (pin "1") (pinfunction "1_1") (pintype "passive"))
      (node (ref "C12") (pin "1") (pinfunction "1_1") (pintype "passive"))
      (node (ref "U1") (pin "25") (pinfunction "VDDC_2_25") (pintype "power_in"))
      (node (ref "U1") (pin "56") (pinfunction "VDDC_56") (pintype "power_in"))
    )
    (net (code "73") (name "V_USB") (class "Default")
      (node (ref "C14") (pin "1") (pinfunction "1_1") (pintype "passive"))
      (node (ref "J2") (pin "2") (pinfunction "2_2") (pintype "passive"))
      (node (ref "S1") (pin "3") (pinfunction "3_3") (pintype "passive"))
      (node (ref "S1") (pin "6") (pinfunction "6_6") (pintype "passive"))
      (node (ref "U$2") (pin "1") (pinfunction "1_1") (pintype "bidirectional"))
      (node (ref "USB") (pin "VCC") (pinfunction "VCC_VCC") (pintype "passive"))
    )
    (net (code "74") (name "XOSC0") (class "Default")
      (node (ref "C2") (pin "2") (pinfunction "2_2") (pintype "passive"))
      (node (ref "U1") (pin "34") (pinfunction "XOSC0_34") (pintype "input"))
      (node (ref "XTAL1") (pin "2") (pinfunction "2_2") (pintype "passive"))
    )
    (net (code "75") (name "XOSC1") (class "Default")
      (node (ref "C1") (pin "2") (pinfunction "2_2") (pintype "passive"))
      (node (ref "U1") (pin "36") (pinfunction "XOSC1_36") (pintype "output"))
      (node (ref "XTAL1") (pin "1") (pinfunction "1_1") (pintype "passive"))
    )
    (net (code "76") (name "unconnected-(IC2-OSCI-Pad27)") (class "Default")
      (node (ref "IC2") (pin "27") (pinfunction "OSCI_27") (pintype "no_connect"))
    )
    (net (code "77") (name "unconnected-(IC2-OSCO-Pad28)") (class "Default")
      (node (ref "IC2") (pin "28") (pinfunction "OSCO_28") (pintype "output"))
    )
    (net (code "78") (name "unconnected-(IC2-TXDEN-Pad13)") (class "Default")
      (node (ref "IC2") (pin "13") (pinfunction "TXDEN_13") (pintype "no_connect"))
    )
    (net (code "79") (name "unconnected-(IC2-~{CTS}-Pad11)") (class "Default")
      (node (ref "IC2") (pin "11") (pinfunction "~{CTS}_11") (pintype "input"))
    )
    (net (code "80") (name "unconnected-(IC2-~{DCD}-Pad10)") (class "Default")
      (node (ref "IC2") (pin "10") (pinfunction "~{DCD}_10") (pintype "no_connect"))
    )
    (net (code "81") (name "unconnected-(IC2-~{DSR}-Pad9)") (class "Default")
      (node (ref "IC2") (pin "9") (pinfunction "~{DSR}_9") (pintype "no_connect"))
    )
    (net (code "82") (name "unconnected-(IC2-~{DTR}-Pad2)") (class "Default")
      (node (ref "IC2") (pin "2") (pinfunction "~{DTR}_2") (pintype "output"))
    )
    (net (code "83") (name "unconnected-(IC2-~{PWREN}-Pad14)") (class "Default")
      (node (ref "IC2") (pin "14") (pinfunction "~{PWREN}_14") (pintype "no_connect"))
    )
    (net (code "84") (name "unconnected-(IC2-~{RESET}-Pad19)") (class "Default")
      (node (ref "IC2") (pin "19") (pinfunction "~{RESET}_19") (pintype "no_connect"))
    )
    (net (code "85") (name "unconnected-(IC2-~{RI}-Pad6)") (class "Default")
      (node (ref "IC2") (pin "6") (pinfunction "~{RI}_6") (pintype "no_connect"))
    )
    (net (code "86") (name "unconnected-(IC2-~{RTS}-Pad3)") (class "Default")
      (node (ref "IC2") (pin "3") (pinfunction "~{RTS}_3") (pintype "output"))
    )
    (net (code "87") (name "unconnected-(IC2-~{RXLED}-Pad22)") (class "Default")
      (node (ref "IC2") (pin "22") (pinfunction "~{RXLED}_22") (pintype "input"))
    )
    (net (code "88") (name "unconnected-(IC2-~{SLEEP}-Pad12)") (class "Default")
      (node (ref "IC2") (pin "12") (pinfunction "~{SLEEP}_12") (pintype "no_connect"))
    )
    (net (code "89") (name "unconnected-(IC2-~{TXLED}-Pad23)") (class "Default")
      (node (ref "IC2") (pin "23") (pinfunction "~{TXLED}_23") (pintype "input"))
    )
    (net (code "90") (name "unconnected-(J3-Pad1)") (class "Default")
      (node (ref "J3") (pin "1") (pinfunction "1_1") (pintype "passive"))
    )
    (net (code "91") (name "unconnected-(J3-Pad2)") (class "Default")
      (node (ref "J3") (pin "2") (pinfunction "2_2") (pintype "passive"))
    )
    (net (code "92") (name "unconnected-(J3-Pad3)") (class "Default")
      (node (ref "J3") (pin "3") (pinfunction "3_3") (pintype "passive"))
    )
    (net (code "93") (name "unconnected-(S1-Pad1)") (class "Default")
      (node (ref "S1") (pin "1") (pinfunction "1_1") (pintype "passive"))
    )
    (net (code "94") (name "unconnected-(S1-Pad4)") (class "Default")
      (node (ref "S1") (pin "4") (pinfunction "4_4") (pintype "passive"))
    )
    (net (code "95") (name "unconnected-(U1-~{HIB}-Pad33)") (class "Default")
      (node (ref "U1") (pin "33") (pinfunction "~{HIB}_33") (pintype "output"))
    )
    (net (code "96") (name "~{DIR1}") (class "Default")
      (node (ref "CR3") (pin "3") (pinfunction "~{AOUT}_3") (pintype "output"))
      (node (ref "MOTOR1") (pin "4") (pinfunction "4_4") (pintype "bidirectional"))
    )
    (net (code "97") (name "~{DIR2}") (class "Default")
      (node (ref "CR3") (pin "5") (pinfunction "~{BOUT}_5") (pintype "output"))
      (node (ref "MOTOR2") (pin "4") (pinfunction "4_4") (pintype "bidirectional"))
    )
    (net (code "98") (name "~{DIR3}") (class "Default")
      (node (ref "CR3") (pin "11") (pinfunction "~{COUT}_11") (pintype "output"))
      (node (ref "MOTOR3") (pin "4") (pinfunction "4_4") (pintype "bidirectional"))
    )
    (net (code "99") (name "~{DIR4}") (class "Default")
      (node (ref "CR3") (pin "13") (pinfunction "~{DOUT}_13") (pintype "output"))
      (node (ref "MOTOR4") (pin "4") (pinfunction "4_4") (pintype "bidirectional"))
    )
    (net (code "100") (name "~{M1}") (class "Default")
      (node (ref "CR1") (pin "3") (pinfunction "~{AOUT}_3") (pintype "output"))
      (node (ref "MOTOR1") (pin "2") (pinfunction "2_2") (pintype "bidirectional"))
    )
    (net (code "101") (name "~{M2}") (class "Default")
      (node (ref "CR1") (pin "5") (pinfunction "~{BOUT}_5") (pintype "output"))
      (node (ref "MOTOR2") (pin "2") (pinfunction "2_2") (pintype "bidirectional"))
    )
    (net (code "102") (name "~{M3}") (class "Default")
      (node (ref "CR1") (pin "11") (pinfunction "~{COUT}_11") (pintype "output"))
      (node (ref "MOTOR3") (pin "2") (pinfunction "2_2") (pintype "bidirectional"))
    )
    (net (code "103") (name "~{M4}") (class "Default")
      (node (ref "CR1") (pin "13") (pinfunction "~{DOUT}_13") (pintype "output"))
      (node (ref "MOTOR4") (pin "2") (pinfunction "2_2") (pintype "bidirectional"))
    )
    (net (code "104") (name "~{RST}") (class "Default")
      (node (ref "B1") (pin "3") (pinfunction "PD2_3") (pintype "bidirectional"))
      (node (ref "B1") (pin "4") (pinfunction "PD2_4") (pintype "bidirectional"))
      (node (ref "J4") (pin "1") (pinfunction "1_1") (pintype "passive"))
      (node (ref "PROG") (pin "5") (pinfunction "5_5") (pintype "bidirectional"))
      (node (ref "R1") (pin "1") (pinfunction "1_1") (pintype "passive"))
      (node (ref "U1") (pin "38") (pinfunction "~{RST}_38") (pintype "input"))
    )
    (net (code "105") (name "~{RS_RX}") (class "Default")
      (node (ref "RS485") (pin "2") (pinfunction "2_2") (pintype "bidirectional"))
      (node (ref "SN75") (pin "7") (pinfunction "B_7") (pintype "output"))
    )
    (net (code "106") (name "~{RS_TX}") (class "Default")
      (node (ref "R29") (pin "1") (pinfunction "1_1") (pintype "passive"))
      (node (ref "R3") (pin "1") (pinfunction "1_1") (pintype "passive"))
      (node (ref "RS485") (pin "4") (pinfunction "4_4") (pintype "bidirectional"))
      (node (ref "SN75") (pin "6") (pinfunction "Z_6") (pintype "output"))
    )
  )
)
